# Atmega328p-AU.net
KiCad netlist of a schematic drawn in Altium Designer
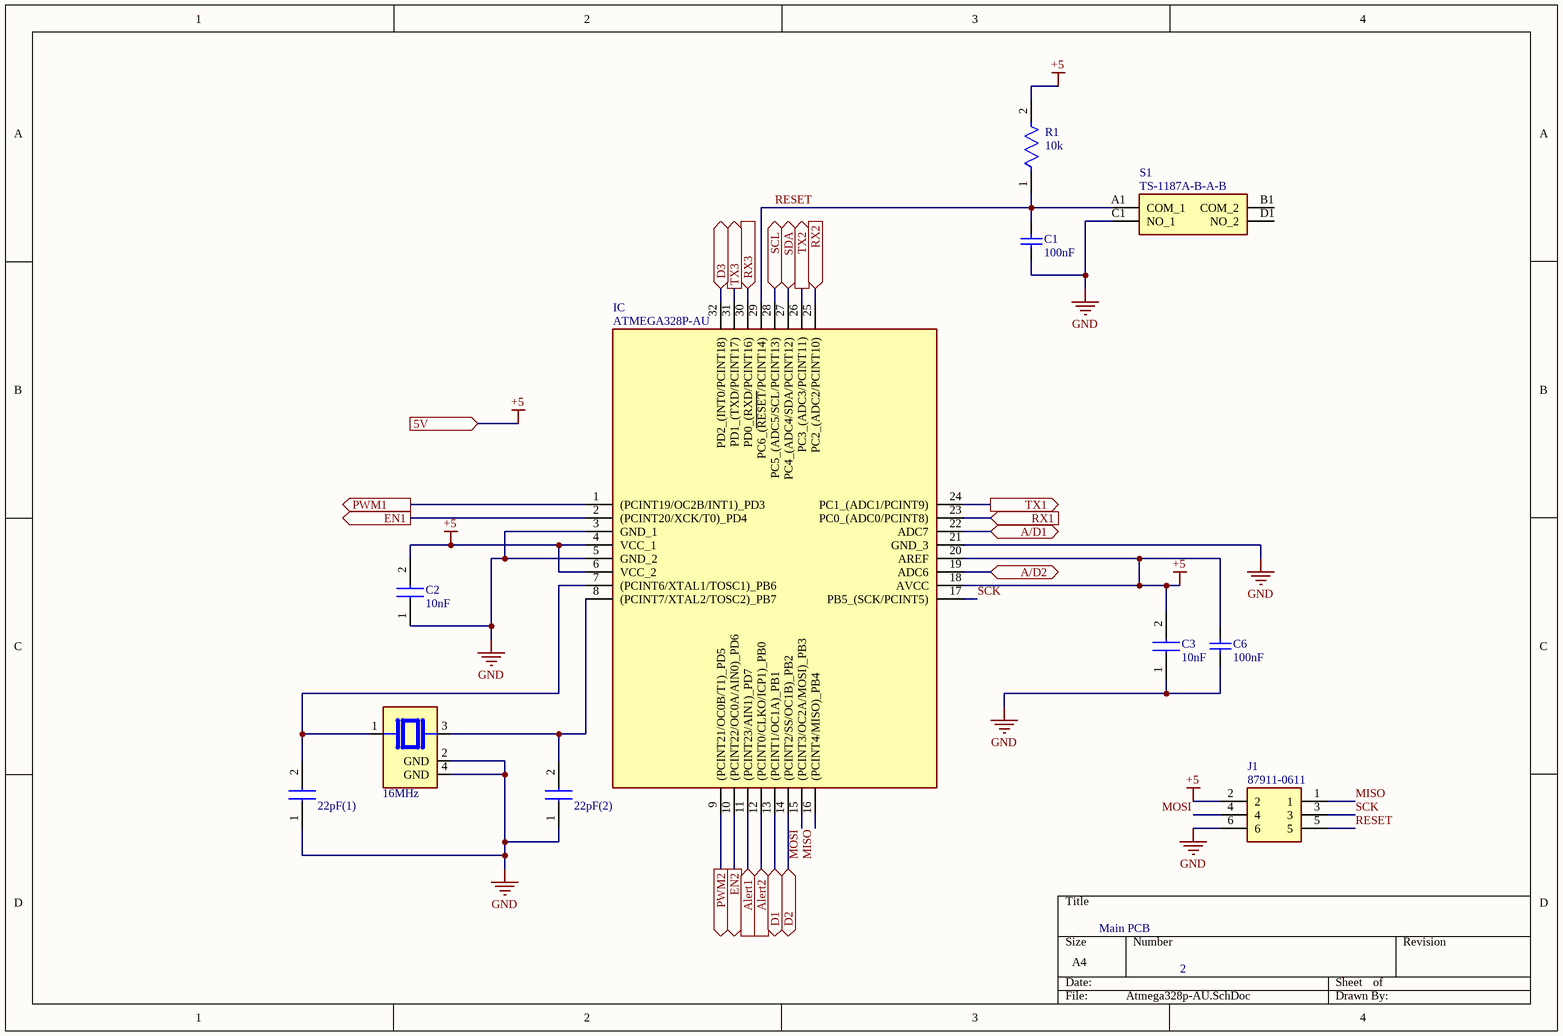
[diagram p0: Atmega328p-AU.SchDoc]

(export (version "E")
  (design (tool "Eeschema 10.0.6"))
  (components
    (comp (ref "16MHz")
      (value "ABM11-16.000MHz-12-N1G-T")
      (footprint "XTAL_ABM11-16.000MHz-12-N1G-T")
      (fields (field (name "MF") "{'manufacturer': u'Abracon LLC'}"))
      (libsource (lib "ABM11-16.000MHz-12-N1G-T") (part "ABM11-16.000MHz-12-N1G-T"))
    )
    (comp (ref "22pF(1)")
      (value "C1206C220JGGACTU")
      (footprint "SamacSys:C1206")
      (description "Capacitor")
      (fields (field (name "MOUSER PART NUMBER") "80-C1206C220JGG"))
      (libsource (lib "*") (part "C1206C220JGGACTU"))
    )
    (comp (ref "22pF(2)")
      (value "C1206C220JGGACTU")
      (footprint "SamacSys:C1206")
      (description "Capacitor")
      (fields (field (name "MOUSER PART NUMBER") "80-C1206C220JGG"))
      (libsource (lib "*") (part "C1206C220JGGACTU"))
    )
    (comp (ref "C1")
      (value "1206GC102KAT1A")
      (footprint "AVX-1206-2_L")
      (description "Chip Capacitor, 1 nF, +/- 10%, -55 to 125 degC, 1206 (3216 Metric), RoHS, Tape and Reel")
      (fields
        (field (name "CAPACITANCE") "100nF")
        (field (name "TOLERANCE") "10%")
        (field (name "MANUFACTURER") "AVX")
      )
      (libsource (lib "Altium Content Vault") (part "CAP-NP-2"))
    )
    (comp (ref "C2")
      (value "10nF")
      (footprint "SamacSys:CAPC3216X94N")
      (description "Capacitor")
      (fields
        (field (name "MANUFACTURER_PART_NUMBER") "KAM31BR81H103KT")
        (field (name "MOUSER PART NUMBER") "581-KAM31BR81H103KT")
      )
      (libsource (lib "*") (part "KAM31BR81H103KT"))
    )
    (comp (ref "C3")
      (value "10nF")
      (footprint "SamacSys:CAPC3216X94N")
      (description "Capacitor")
      (fields
        (field (name "MANUFACTURER_PART_NUMBER") "KAM31BR81H103KT")
        (field (name "MOUSER PART NUMBER") "581-KAM31BR81H103KT")
      )
      (libsource (lib "*") (part "KAM31BR81H103KT"))
    )
    (comp (ref "C6")
      (value "1206GC102KAT1A")
      (footprint "AVX-1206-2_L")
      (description "Chip Capacitor, 1 nF, +/- 10%, -55 to 125 degC, 1206 (3216 Metric), RoHS, Tape and Reel")
      (fields
        (field (name "CAPACITANCE") "100nF")
        (field (name "TOLERANCE") "10%")
        (field (name "MANUFACTURER") "AVX")
      )
      (libsource (lib "Altium Content Vault") (part "CAP-NP-2"))
    )
    (comp (ref "IC")
      (value "ATMEGA328P-AU")
      (footprint "SamacSys:QFP80P900X900X120-32N")
      (description "Integrated Circuit")
      (fields (field (name "MOUSER PART NUMBER") "556-ATMEGA328P-AU"))
      (libsource (lib "*") (part "ATMEGA328P-AU"))
    )
    (comp (ref "J1")
      (value "87911-0611")
      (footprint "SamacSys:879110611")
      (description "Connector")
      (fields (field (name "MOUSER PART NUMBER") "538-87911-0611"))
      (libsource (lib "SamacSys") (part "87911-0611"))
    )
    (comp (ref "R1")
      (value "10k")
      (footprint "FP-RC1206-MFG")
      (description "RES SMD 0 OHM JUMPER 1/4W 1206")
      (fields
        (field (name "MANUFACTURER PART NUMBER") "RC1206JR-070RL")
        (field (name "MANUFACTURER") "YAGEO")
      )
      (libsource (lib "Altium Content Vault") (part "1029c3af85768c4190bb7ad29bc67b5"))
    )
    (comp (ref "S1")
      (value "TS-1187A-B-A-B")
      (footprint "SamacSys:TS1187ABAB")
      (description "Switch")
      (libsource (lib "*") (part "TS-1187A-B-A-B"))
    )
  )
  (nets
    (net (code "1") (name "+5") (class "Default")
      (node (ref "C2") (pin "2") (pinfunction "2_2") (pintype "passive"))
      (node (ref "C3") (pin "2") (pinfunction "2_2") (pintype "passive"))
      (node (ref "C6") (pin "2") (pinfunction "2_2") (pintype "passive"))
      (node (ref "IC") (pin "18") (pinfunction "AVCC_18") (pintype "passive"))
      (node (ref "IC") (pin "20") (pinfunction "AREF_20") (pintype "passive"))
      (node (ref "IC") (pin "4") (pinfunction "VCC_1_4") (pintype "passive"))
      (node (ref "IC") (pin "6") (pinfunction "VCC_2_6") (pintype "passive"))
      (node (ref "J1") (pin "2") (pinfunction "2_2") (pintype "passive"))
      (node (ref "R1") (pin "2") (pinfunction "2_2") (pintype "passive"))
    )
    (net (code "2") (name "/Alert1") (class "Default")
      (node (ref "IC") (pin "11") (pinfunction "(PCINT23/AIN1)_PD7_11") (pintype "passive"))
    )
    (net (code "3") (name "/Alert2") (class "Default")
      (node (ref "IC") (pin "12") (pinfunction "(PCINT0/CLKO/ICP1)_PB0_12") (pintype "passive"))
    )
    (net (code "4") (name "/A{slash}D1") (class "Default")
      (node (ref "IC") (pin "22") (pinfunction "ADC7_22") (pintype "passive"))
    )
    (net (code "5") (name "/A{slash}D2") (class "Default")
      (node (ref "IC") (pin "19") (pinfunction "ADC6_19") (pintype "passive"))
    )
    (net (code "6") (name "/D1") (class "Default")
      (node (ref "IC") (pin "13") (pinfunction "(PCINT1/OC1A)_PB1_13") (pintype "passive"))
    )
    (net (code "7") (name "/D2") (class "Default")
      (node (ref "IC") (pin "14") (pinfunction "(PCINT2/SS/OC1B)_PB2_14") (pintype "passive"))
    )
    (net (code "8") (name "/D3") (class "Default")
      (node (ref "IC") (pin "32") (pinfunction "PD2_(INT0/PCINT18)_32") (pintype "passive"))
    )
    (net (code "9") (name "/EN1") (class "Default")
      (node (ref "IC") (pin "2") (pinfunction "(PCINT20/XCK/T0)_PD4_2") (pintype "passive"))
    )
    (net (code "10") (name "/EN2") (class "Default")
      (node (ref "IC") (pin "10") (pinfunction "(PCINT22/OC0A/AIN0)_PD6_10") (pintype "passive"))
    )
    (net (code "11") (name "/MISO") (class "Default")
      (node (ref "IC") (pin "16") (pinfunction "(PCINT4/MISO)_PB4_16") (pintype "passive"))
      (node (ref "J1") (pin "1") (pinfunction "1_1") (pintype "passive"))
    )
    (net (code "12") (name "/MOSI") (class "Default")
      (node (ref "IC") (pin "15") (pinfunction "(PCINT3/OC2A/MOSI)_PB3_15") (pintype "passive"))
      (node (ref "J1") (pin "4") (pinfunction "4_4") (pintype "passive"))
    )
    (net (code "13") (name "/PWM1") (class "Default")
      (node (ref "IC") (pin "1") (pinfunction "(PCINT19/OC2B/INT1)_PD3_1") (pintype "passive"))
    )
    (net (code "14") (name "/PWM2") (class "Default")
      (node (ref "IC") (pin "9") (pinfunction "(PCINT21/OC0B/T1)_PD5_9") (pintype "passive"))
    )
    (net (code "15") (name "/RESET") (class "Default")
      (node (ref "C1") (pin "2") (pinfunction "2_2") (pintype "passive"))
      (node (ref "IC") (pin "29") (pinfunction "PC6_(~{RESET}/PCINT14)_29") (pintype "passive"))
      (node (ref "J1") (pin "5") (pinfunction "5_5") (pintype "passive"))
      (node (ref "R1") (pin "1") (pinfunction "1_1") (pintype "passive"))
      (node (ref "S1") (pin "A1") (pinfunction "COM_1_A1") (pintype "passive"))
    )
    (net (code "16") (name "/RX1") (class "Default")
      (node (ref "IC") (pin "23") (pinfunction "PC0_(ADC0/PCINT8)_23") (pintype "passive"))
    )
    (net (code "17") (name "/RX2") (class "Default")
      (node (ref "IC") (pin "25") (pinfunction "PC2_(ADC2/PCINT10)_25") (pintype "passive"))
    )
    (net (code "18") (name "/RX3") (class "Default")
      (node (ref "IC") (pin "30") (pinfunction "PD0_(RXD/PCINT16)_30") (pintype "passive"))
    )
    (net (code "19") (name "/SCK") (class "Default")
      (node (ref "IC") (pin "17") (pinfunction "PB5_(SCK/PCINT5)_17") (pintype "passive"))
      (node (ref "J1") (pin "3") (pinfunction "3_3") (pintype "passive"))
    )
    (net (code "20") (name "/SCL") (class "Default")
      (node (ref "IC") (pin "28") (pinfunction "PC5_(ADC5/SCL/PCINT13)_28") (pintype "passive"))
    )
    (net (code "21") (name "/SDA") (class "Default")
      (node (ref "IC") (pin "27") (pinfunction "PC4_(ADC4/SDA/PCINT12)_27") (pintype "passive"))
    )
    (net (code "22") (name "/TX1") (class "Default")
      (node (ref "IC") (pin "24") (pinfunction "PC1_(ADC1/PCINT9)_24") (pintype "passive"))
    )
    (net (code "23") (name "/TX2") (class "Default")
      (node (ref "IC") (pin "26") (pinfunction "PC3_(ADC3/PCINT11)_26") (pintype "passive"))
    )
    (net (code "24") (name "/TX3") (class "Default")
      (node (ref "IC") (pin "31") (pinfunction "PD1_(TXD/PCINT17)_31") (pintype "passive"))
    )
    (net (code "25") (name "GND") (class "Default")
      (node (ref "16MHz") (pin "2") (pinfunction "GND_2") (pintype "power_in"))
      (node (ref "16MHz") (pin "4") (pinfunction "GND_4") (pintype "power_in"))
      (node (ref "22pF(1)") (pin "1") (pinfunction "1_1") (pintype "passive"))
      (node (ref "22pF(2)") (pin "1") (pinfunction "1_1") (pintype "passive"))
      (node (ref "C1") (pin "1") (pinfunction "1_1") (pintype "passive"))
      (node (ref "C2") (pin "1") (pinfunction "1_1") (pintype "passive"))
      (node (ref "C3") (pin "1") (pinfunction "1_1") (pintype "passive"))
      (node (ref "C6") (pin "1") (pinfunction "1_1") (pintype "passive"))
      (node (ref "IC") (pin "21") (pinfunction "GND_3_21") (pintype "passive"))
      (node (ref "IC") (pin "3") (pinfunction "GND_1_3") (pintype "passive"))
      (node (ref "IC") (pin "5") (pinfunction "GND_2_5") (pintype "passive"))
      (node (ref "J1") (pin "6") (pinfunction "6_6") (pintype "passive"))
      (node (ref "S1") (pin "C1") (pinfunction "NO_1_C1") (pintype "passive"))
    )
    (net (code "26") (name "Net-(16MHz-2)") (class "Default")
      (node (ref "16MHz") (pin "3") (pinfunction "2_3") (pintype "passive"))
      (node (ref "22pF(2)") (pin "2") (pinfunction "2_2") (pintype "passive"))
      (node (ref "IC") (pin "8") (pinfunction "(PCINT7/XTAL2/TOSC2)_PB7_8") (pintype "passive"))
    )
    (net (code "27") (name "Net-(IC-(PCINT6{slash}XTAL1{slash}TOSC1)_PB6)") (class "Default")
      (node (ref "16MHz") (pin "1") (pinfunction "1_1") (pintype "passive"))
      (node (ref "22pF(1)") (pin "2") (pinfunction "2_2") (pintype "passive"))
      (node (ref "IC") (pin "7") (pinfunction "(PCINT6/XTAL1/TOSC1)_PB6_7") (pintype "passive"))
    )
    (net (code "28") (name "unconnected-(S1-COM_2-PadB1)") (class "Default")
      (node (ref "S1") (pin "B1") (pinfunction "COM_2_B1") (pintype "passive"))
    )
    (net (code "29") (name "unconnected-(S1-NO_2-PadD1)") (class "Default")
      (node (ref "S1") (pin "D1") (pinfunction "NO_2_D1") (pintype "passive"))
    )
  )
)
